# SCH_ELLIE_DISPLAY_PANEL_2023-12-06.net
KiCad netlist of a schematic drawn in EasyEDA
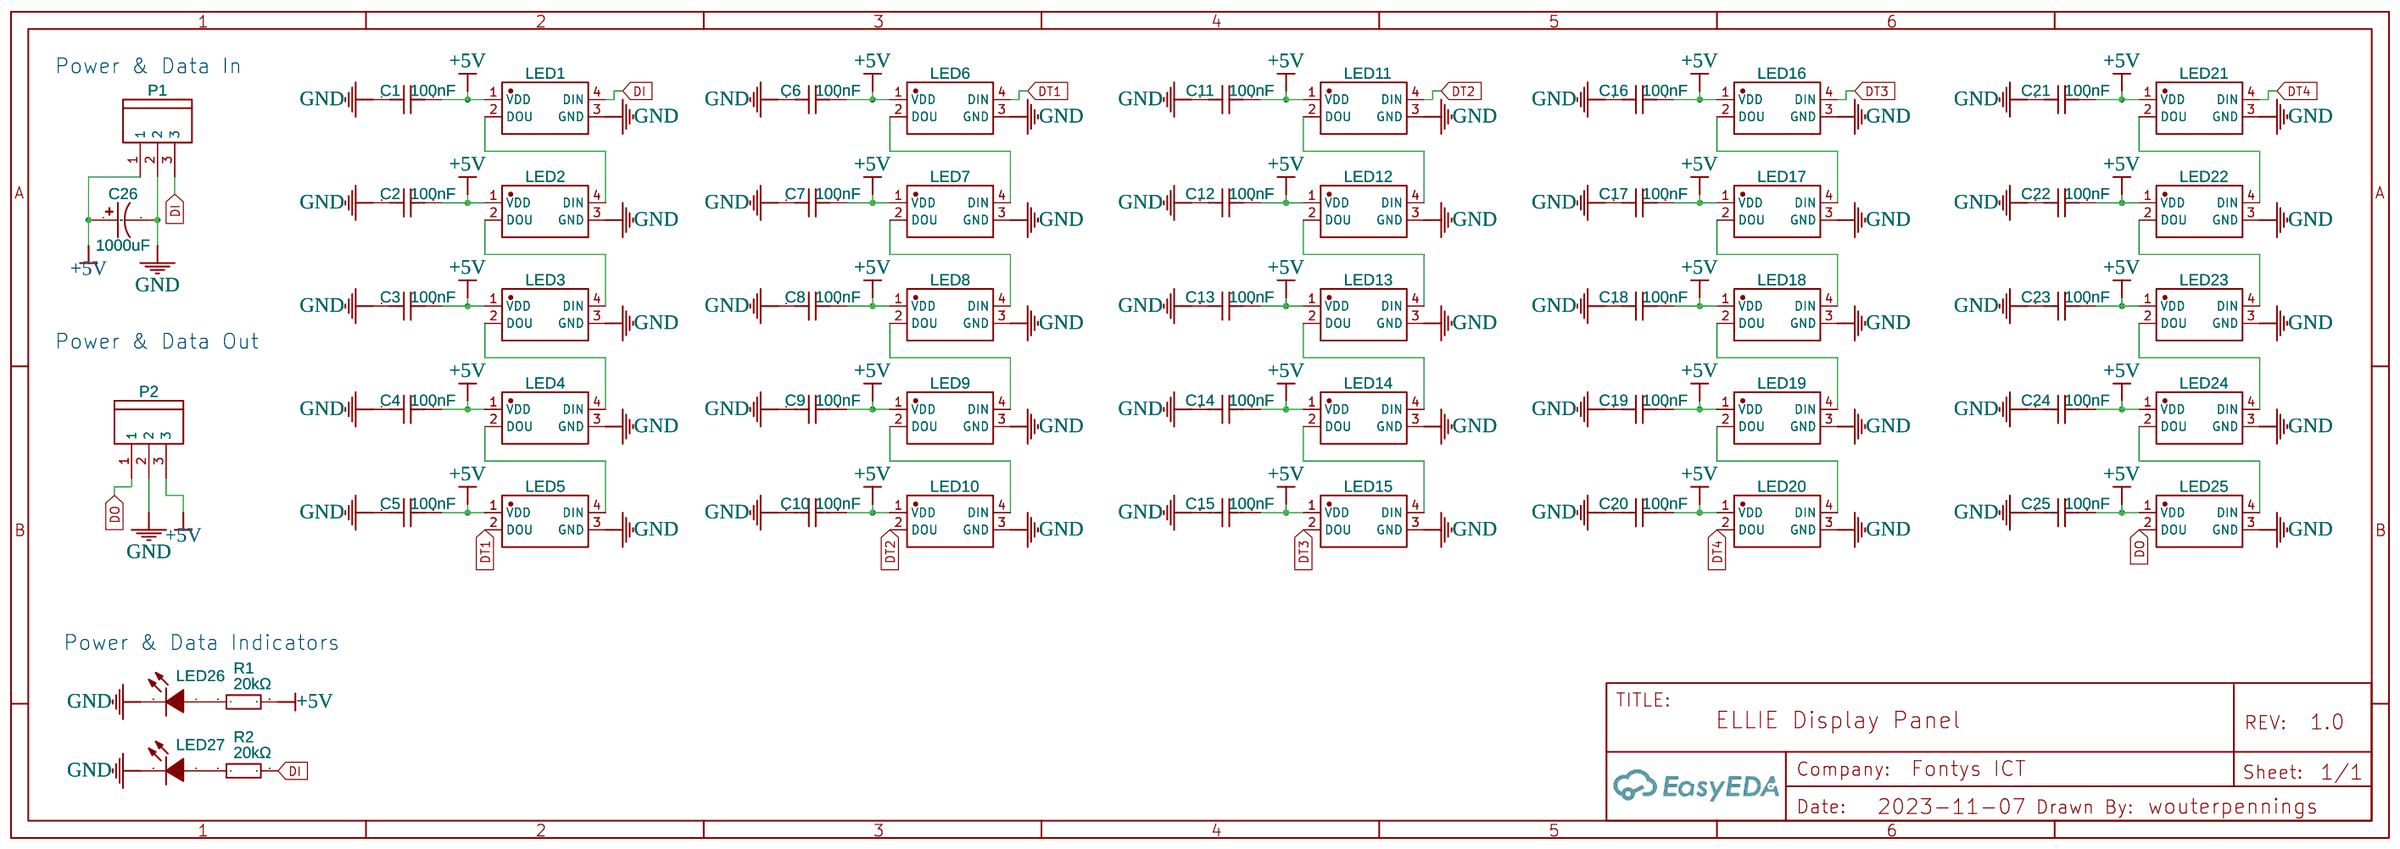
[diagram p0: schematic sheet]

(export (version "E")
  (design (tool "Eeschema 10.0.6"))
  (components
    (comp (ref "C1")
      (value "100nF")
      (fields
        (field (name "Manufacturer Part") "CC0402KRX7R7BB104")
        (field (name "Manufacturer") "YAGEO(国巨)")
      )
      (libsource (lib "") (part "CC0402KRX7R7BB104"))
    )
    (comp (ref "C2")
      (value "100nF")
      (fields
        (field (name "Manufacturer Part") "CC0402KRX7R7BB104")
        (field (name "Manufacturer") "YAGEO(国巨)")
      )
      (libsource (lib "") (part "CC0402KRX7R7BB104"))
    )
    (comp (ref "C3")
      (value "100nF")
      (fields
        (field (name "Manufacturer Part") "CC0402KRX7R7BB104")
        (field (name "Manufacturer") "YAGEO(国巨)")
      )
      (libsource (lib "") (part "CC0402KRX7R7BB104"))
    )
    (comp (ref "C4")
      (value "100nF")
      (fields
        (field (name "Manufacturer Part") "CC0402KRX7R7BB104")
        (field (name "Manufacturer") "YAGEO(国巨)")
      )
      (libsource (lib "") (part "CC0402KRX7R7BB104"))
    )
    (comp (ref "C5")
      (value "100nF")
      (fields
        (field (name "Manufacturer Part") "CC0402KRX7R7BB104")
        (field (name "Manufacturer") "YAGEO(国巨)")
      )
      (libsource (lib "") (part "CC0402KRX7R7BB104"))
    )
    (comp (ref "C6")
      (value "100nF")
      (fields
        (field (name "Manufacturer Part") "CC0402KRX7R7BB104")
        (field (name "Manufacturer") "YAGEO(国巨)")
      )
      (libsource (lib "") (part "CC0402KRX7R7BB104"))
    )
    (comp (ref "C7")
      (value "100nF")
      (fields
        (field (name "Manufacturer Part") "CC0402KRX7R7BB104")
        (field (name "Manufacturer") "YAGEO(国巨)")
      )
      (libsource (lib "") (part "CC0402KRX7R7BB104"))
    )
    (comp (ref "C8")
      (value "100nF")
      (fields
        (field (name "Manufacturer Part") "CC0402KRX7R7BB104")
        (field (name "Manufacturer") "YAGEO(国巨)")
      )
      (libsource (lib "") (part "CC0402KRX7R7BB104"))
    )
    (comp (ref "C9")
      (value "100nF")
      (fields
        (field (name "Manufacturer Part") "CC0402KRX7R7BB104")
        (field (name "Manufacturer") "YAGEO(国巨)")
      )
      (libsource (lib "") (part "CC0402KRX7R7BB104"))
    )
    (comp (ref "C10")
      (value "100nF")
      (fields
        (field (name "Manufacturer Part") "CC0402KRX7R7BB104")
        (field (name "Manufacturer") "YAGEO(国巨)")
      )
      (libsource (lib "") (part "CC0402KRX7R7BB104"))
    )
    (comp (ref "C11")
      (value "100nF")
      (fields
        (field (name "Manufacturer Part") "CC0402KRX7R7BB104")
        (field (name "Manufacturer") "YAGEO(国巨)")
      )
      (libsource (lib "") (part "CC0402KRX7R7BB104"))
    )
    (comp (ref "C12")
      (value "100nF")
      (fields
        (field (name "Manufacturer Part") "CC0402KRX7R7BB104")
        (field (name "Manufacturer") "YAGEO(国巨)")
      )
      (libsource (lib "") (part "CC0402KRX7R7BB104"))
    )
    (comp (ref "C13")
      (value "100nF")
      (fields
        (field (name "Manufacturer Part") "CC0402KRX7R7BB104")
        (field (name "Manufacturer") "YAGEO(国巨)")
      )
      (libsource (lib "") (part "CC0402KRX7R7BB104"))
    )
    (comp (ref "C14")
      (value "100nF")
      (fields
        (field (name "Manufacturer Part") "CC0402KRX7R7BB104")
        (field (name "Manufacturer") "YAGEO(国巨)")
      )
      (libsource (lib "") (part "CC0402KRX7R7BB104"))
    )
    (comp (ref "C15")
      (value "100nF")
      (fields
        (field (name "Manufacturer Part") "CC0402KRX7R7BB104")
        (field (name "Manufacturer") "YAGEO(国巨)")
      )
      (libsource (lib "") (part "CC0402KRX7R7BB104"))
    )
    (comp (ref "C16")
      (value "100nF")
      (fields
        (field (name "Manufacturer Part") "CC0402KRX7R7BB104")
        (field (name "Manufacturer") "YAGEO(国巨)")
      )
      (libsource (lib "") (part "CC0402KRX7R7BB104"))
    )
    (comp (ref "C17")
      (value "100nF")
      (fields
        (field (name "Manufacturer Part") "CC0402KRX7R7BB104")
        (field (name "Manufacturer") "YAGEO(国巨)")
      )
      (libsource (lib "") (part "CC0402KRX7R7BB104"))
    )
    (comp (ref "C18")
      (value "100nF")
      (fields
        (field (name "Manufacturer Part") "CC0402KRX7R7BB104")
        (field (name "Manufacturer") "YAGEO(国巨)")
      )
      (libsource (lib "") (part "CC0402KRX7R7BB104"))
    )
    (comp (ref "C19")
      (value "100nF")
      (fields
        (field (name "Manufacturer Part") "CC0402KRX7R7BB104")
        (field (name "Manufacturer") "YAGEO(国巨)")
      )
      (libsource (lib "") (part "CC0402KRX7R7BB104"))
    )
    (comp (ref "C20")
      (value "100nF")
      (fields
        (field (name "Manufacturer Part") "CC0402KRX7R7BB104")
        (field (name "Manufacturer") "YAGEO(国巨)")
      )
      (libsource (lib "") (part "CC0402KRX7R7BB104"))
    )
    (comp (ref "C21")
      (value "100nF")
      (fields
        (field (name "Manufacturer Part") "CC0402KRX7R7BB104")
        (field (name "Manufacturer") "YAGEO(国巨)")
      )
      (libsource (lib "") (part "CC0402KRX7R7BB104"))
    )
    (comp (ref "C22")
      (value "100nF")
      (fields
        (field (name "Manufacturer Part") "CC0402KRX7R7BB104")
        (field (name "Manufacturer") "YAGEO(国巨)")
      )
      (libsource (lib "") (part "CC0402KRX7R7BB104"))
    )
    (comp (ref "C23")
      (value "100nF")
      (fields
        (field (name "Manufacturer Part") "CC0402KRX7R7BB104")
        (field (name "Manufacturer") "YAGEO(国巨)")
      )
      (libsource (lib "") (part "CC0402KRX7R7BB104"))
    )
    (comp (ref "C24")
      (value "100nF")
      (fields
        (field (name "Manufacturer Part") "CC0402KRX7R7BB104")
        (field (name "Manufacturer") "YAGEO(国巨)")
      )
      (libsource (lib "") (part "CC0402KRX7R7BB104"))
    )
    (comp (ref "C25")
      (value "100nF")
      (fields
        (field (name "Manufacturer Part") "CC0402KRX7R7BB104")
        (field (name "Manufacturer") "YAGEO(国巨)")
      )
      (libsource (lib "") (part "CC0402KRX7R7BB104"))
    )
    (comp (ref "C26")
      (value "1000uF")
      (fields
        (field (name "Manufacturer Part") "01EC4294SHC1000UF25V")
        (field (name "Manufacturer") "KNSCHA(科尼盛)")
      )
      (libsource (lib "") (part "01EC4294SHC1000UF25V"))
    )
    (comp (ref "LED1")
      (value "XL-5050RGBC-WS2812B")
      (fields (field (name "Manufacturer") "XINGLIGHT(成兴光)"))
      (libsource (lib "") (part "XL-5050RGBC-WS2812B"))
    )
    (comp (ref "LED2")
      (value "XL-5050RGBC-WS2812B")
      (fields (field (name "Manufacturer") "XINGLIGHT(成兴光)"))
      (libsource (lib "") (part "XL-5050RGBC-WS2812B"))
    )
    (comp (ref "LED3")
      (value "XL-5050RGBC-WS2812B")
      (fields (field (name "Manufacturer") "XINGLIGHT(成兴光)"))
      (libsource (lib "") (part "XL-5050RGBC-WS2812B"))
    )
    (comp (ref "LED4")
      (value "XL-5050RGBC-WS2812B")
      (fields (field (name "Manufacturer") "XINGLIGHT(成兴光)"))
      (libsource (lib "") (part "XL-5050RGBC-WS2812B"))
    )
    (comp (ref "LED5")
      (value "XL-5050RGBC-WS2812B")
      (fields (field (name "Manufacturer") "XINGLIGHT(成兴光)"))
      (libsource (lib "") (part "XL-5050RGBC-WS2812B"))
    )
    (comp (ref "LED6")
      (value "XL-5050RGBC-WS2812B")
      (fields (field (name "Manufacturer") "XINGLIGHT(成兴光)"))
      (libsource (lib "") (part "XL-5050RGBC-WS2812B"))
    )
    (comp (ref "LED7")
      (value "XL-5050RGBC-WS2812B")
      (fields (field (name "Manufacturer") "XINGLIGHT(成兴光)"))
      (libsource (lib "") (part "XL-5050RGBC-WS2812B"))
    )
    (comp (ref "LED8")
      (value "XL-5050RGBC-WS2812B")
      (fields (field (name "Manufacturer") "XINGLIGHT(成兴光)"))
      (libsource (lib "") (part "XL-5050RGBC-WS2812B"))
    )
    (comp (ref "LED9")
      (value "XL-5050RGBC-WS2812B")
      (fields (field (name "Manufacturer") "XINGLIGHT(成兴光)"))
      (libsource (lib "") (part "XL-5050RGBC-WS2812B"))
    )
    (comp (ref "LED10")
      (value "XL-5050RGBC-WS2812B")
      (fields (field (name "Manufacturer") "XINGLIGHT(成兴光)"))
      (libsource (lib "") (part "XL-5050RGBC-WS2812B"))
    )
    (comp (ref "LED11")
      (value "XL-5050RGBC-WS2812B")
      (fields (field (name "Manufacturer") "XINGLIGHT(成兴光)"))
      (libsource (lib "") (part "XL-5050RGBC-WS2812B"))
    )
    (comp (ref "LED12")
      (value "XL-5050RGBC-WS2812B")
      (fields (field (name "Manufacturer") "XINGLIGHT(成兴光)"))
      (libsource (lib "") (part "XL-5050RGBC-WS2812B"))
    )
    (comp (ref "LED13")
      (value "XL-5050RGBC-WS2812B")
      (fields (field (name "Manufacturer") "XINGLIGHT(成兴光)"))
      (libsource (lib "") (part "XL-5050RGBC-WS2812B"))
    )
    (comp (ref "LED14")
      (value "XL-5050RGBC-WS2812B")
      (fields (field (name "Manufacturer") "XINGLIGHT(成兴光)"))
      (libsource (lib "") (part "XL-5050RGBC-WS2812B"))
    )
    (comp (ref "LED15")
      (value "XL-5050RGBC-WS2812B")
      (fields (field (name "Manufacturer") "XINGLIGHT(成兴光)"))
      (libsource (lib "") (part "XL-5050RGBC-WS2812B"))
    )
    (comp (ref "LED16")
      (value "XL-5050RGBC-WS2812B")
      (fields (field (name "Manufacturer") "XINGLIGHT(成兴光)"))
      (libsource (lib "") (part "XL-5050RGBC-WS2812B"))
    )
    (comp (ref "LED17")
      (value "XL-5050RGBC-WS2812B")
      (fields (field (name "Manufacturer") "XINGLIGHT(成兴光)"))
      (libsource (lib "") (part "XL-5050RGBC-WS2812B"))
    )
    (comp (ref "LED18")
      (value "XL-5050RGBC-WS2812B")
      (fields (field (name "Manufacturer") "XINGLIGHT(成兴光)"))
      (libsource (lib "") (part "XL-5050RGBC-WS2812B"))
    )
    (comp (ref "LED19")
      (value "XL-5050RGBC-WS2812B")
      (fields (field (name "Manufacturer") "XINGLIGHT(成兴光)"))
      (libsource (lib "") (part "XL-5050RGBC-WS2812B"))
    )
    (comp (ref "LED20")
      (value "XL-5050RGBC-WS2812B")
      (fields (field (name "Manufacturer") "XINGLIGHT(成兴光)"))
      (libsource (lib "") (part "XL-5050RGBC-WS2812B"))
    )
    (comp (ref "LED21")
      (value "XL-5050RGBC-WS2812B")
      (fields (field (name "Manufacturer") "XINGLIGHT(成兴光)"))
      (libsource (lib "") (part "XL-5050RGBC-WS2812B"))
    )
    (comp (ref "LED22")
      (value "XL-5050RGBC-WS2812B")
      (fields (field (name "Manufacturer") "XINGLIGHT(成兴光)"))
      (libsource (lib "") (part "XL-5050RGBC-WS2812B"))
    )
    (comp (ref "LED23")
      (value "XL-5050RGBC-WS2812B")
      (fields (field (name "Manufacturer") "XINGLIGHT(成兴光)"))
      (libsource (lib "") (part "XL-5050RGBC-WS2812B"))
    )
    (comp (ref "LED24")
      (value "XL-5050RGBC-WS2812B")
      (fields (field (name "Manufacturer") "XINGLIGHT(成兴光)"))
      (libsource (lib "") (part "XL-5050RGBC-WS2812B"))
    )
    (comp (ref "LED25")
      (value "XL-5050RGBC-WS2812B")
      (fields (field (name "Manufacturer") "XINGLIGHT(成兴光)"))
      (libsource (lib "") (part "XL-5050RGBC-WS2812B"))
    )
    (comp (ref "LED26")
      (value "SZYY0805R")
      (fields (field (name "Manufacturer") "yongyu(永裕光电)"))
      (libsource (lib "") (part "SZYY0805R"))
    )
    (comp (ref "LED27")
      (value "SZYY0805R")
      (fields (field (name "Manufacturer") "yongyu(永裕光电)"))
      (libsource (lib "") (part "SZYY0805R"))
    )
    (comp (ref "P1")
      (value "WJ500V-5.08-3P-14-00A")
      (fields
        (field (name "Manufacturer Part") "WJ500V-5.08-3P")
        (field (name "Manufacturer") "KANGNEX(康奈克斯电气)")
      )
      (libsource (lib "") (part "WJ500V-5.08-3P-14-00A"))
    )
    (comp (ref "P2")
      (value "WJ500V-5.08-3P-14-00A")
      (fields
        (field (name "Manufacturer Part") "WJ500V-5.08-3P")
        (field (name "Manufacturer") "KANGNEX(康奈克斯电气)")
      )
      (libsource (lib "") (part "WJ500V-5.08-3P-14-00A"))
    )
    (comp (ref "R1")
      (value "20kΩ")
      (fields
        (field (name "Manufacturer Part") "0603WAF2002T5E")
        (field (name "Manufacturer") "UNI-ROYAL(厚声)")
      )
      (libsource (lib "") (part "0603WAF2002T5E"))
    )
    (comp (ref "R2")
      (value "20kΩ")
      (fields
        (field (name "Manufacturer Part") "0603WAF2002T5E")
        (field (name "Manufacturer") "UNI-ROYAL(厚声)")
      )
      (libsource (lib "") (part "0603WAF2002T5E"))
    )
  )
  (nets
    (net (code "1") (name "+5V") (class "Default")
      (node (ref "C1") (pin "2") (pinfunction "2_2") (pintype "unspecified"))
      (node (ref "C10") (pin "2") (pinfunction "2_2") (pintype "unspecified"))
      (node (ref "C11") (pin "2") (pinfunction "2_2") (pintype "unspecified"))
      (node (ref "C12") (pin "2") (pinfunction "2_2") (pintype "unspecified"))
      (node (ref "C13") (pin "2") (pinfunction "2_2") (pintype "unspecified"))
      (node (ref "C14") (pin "2") (pinfunction "2_2") (pintype "unspecified"))
      (node (ref "C15") (pin "2") (pinfunction "2_2") (pintype "unspecified"))
      (node (ref "C16") (pin "2") (pinfunction "2_2") (pintype "unspecified"))
      (node (ref "C17") (pin "2") (pinfunction "2_2") (pintype "unspecified"))
      (node (ref "C18") (pin "2") (pinfunction "2_2") (pintype "unspecified"))
      (node (ref "C19") (pin "2") (pinfunction "2_2") (pintype "unspecified"))
      (node (ref "C2") (pin "2") (pinfunction "2_2") (pintype "unspecified"))
      (node (ref "C20") (pin "2") (pinfunction "2_2") (pintype "unspecified"))
      (node (ref "C21") (pin "2") (pinfunction "2_2") (pintype "unspecified"))
      (node (ref "C22") (pin "2") (pinfunction "2_2") (pintype "unspecified"))
      (node (ref "C23") (pin "2") (pinfunction "2_2") (pintype "unspecified"))
      (node (ref "C24") (pin "2") (pinfunction "2_2") (pintype "unspecified"))
      (node (ref "C25") (pin "2") (pinfunction "2_2") (pintype "unspecified"))
      (node (ref "C26") (pin "1") (pinfunction "1_1") (pintype "unspecified"))
      (node (ref "C3") (pin "2") (pinfunction "2_2") (pintype "unspecified"))
      (node (ref "C4") (pin "2") (pinfunction "2_2") (pintype "unspecified"))
      (node (ref "C5") (pin "2") (pinfunction "2_2") (pintype "unspecified"))
      (node (ref "C6") (pin "2") (pinfunction "2_2") (pintype "unspecified"))
      (node (ref "C7") (pin "2") (pinfunction "2_2") (pintype "unspecified"))
      (node (ref "C8") (pin "2") (pinfunction "2_2") (pintype "unspecified"))
      (node (ref "C9") (pin "2") (pinfunction "2_2") (pintype "unspecified"))
      (node (ref "LED1") (pin "1") (pinfunction "VDD_1") (pintype "unspecified"))
      (node (ref "LED10") (pin "1") (pinfunction "VDD_1") (pintype "unspecified"))
      (node (ref "LED11") (pin "1") (pinfunction "VDD_1") (pintype "unspecified"))
      (node (ref "LED12") (pin "1") (pinfunction "VDD_1") (pintype "unspecified"))
      (node (ref "LED13") (pin "1") (pinfunction "VDD_1") (pintype "unspecified"))
      (node (ref "LED14") (pin "1") (pinfunction "VDD_1") (pintype "unspecified"))
      (node (ref "LED15") (pin "1") (pinfunction "VDD_1") (pintype "unspecified"))
      (node (ref "LED16") (pin "1") (pinfunction "VDD_1") (pintype "unspecified"))
      (node (ref "LED17") (pin "1") (pinfunction "VDD_1") (pintype "unspecified"))
      (node (ref "LED18") (pin "1") (pinfunction "VDD_1") (pintype "unspecified"))
      (node (ref "LED19") (pin "1") (pinfunction "VDD_1") (pintype "unspecified"))
      (node (ref "LED2") (pin "1") (pinfunction "VDD_1") (pintype "unspecified"))
      (node (ref "LED20") (pin "1") (pinfunction "VDD_1") (pintype "unspecified"))
      (node (ref "LED21") (pin "1") (pinfunction "VDD_1") (pintype "unspecified"))
      (node (ref "LED22") (pin "1") (pinfunction "VDD_1") (pintype "unspecified"))
      (node (ref "LED23") (pin "1") (pinfunction "VDD_1") (pintype "unspecified"))
      (node (ref "LED24") (pin "1") (pinfunction "VDD_1") (pintype "unspecified"))
      (node (ref "LED25") (pin "1") (pinfunction "VDD_1") (pintype "unspecified"))
      (node (ref "LED3") (pin "1") (pinfunction "VDD_1") (pintype "unspecified"))
      (node (ref "LED4") (pin "1") (pinfunction "VDD_1") (pintype "unspecified"))
      (node (ref "LED5") (pin "1") (pinfunction "VDD_1") (pintype "unspecified"))
      (node (ref "LED6") (pin "1") (pinfunction "VDD_1") (pintype "unspecified"))
      (node (ref "LED7") (pin "1") (pinfunction "VDD_1") (pintype "unspecified"))
      (node (ref "LED8") (pin "1") (pinfunction "VDD_1") (pintype "unspecified"))
      (node (ref "LED9") (pin "1") (pinfunction "VDD_1") (pintype "unspecified"))
      (node (ref "P1") (pin "1") (pinfunction "1_1") (pintype "unspecified"))
      (node (ref "P2") (pin "3") (pinfunction "3_3") (pintype "unspecified"))
      (node (ref "R1") (pin "2") (pinfunction "2_2") (pintype "input"))
    )
    (net (code "2") (name "DI") (class "Default")
      (node (ref "LED1") (pin "4") (pinfunction "DIN_4") (pintype "unspecified"))
      (node (ref "P1") (pin "3") (pinfunction "3_3") (pintype "unspecified"))
      (node (ref "R2") (pin "2") (pinfunction "2_2") (pintype "input"))
    )
    (net (code "3") (name "DO") (class "Default")
      (node (ref "LED25") (pin "2") (pinfunction "DOU_2") (pintype "unspecified"))
      (node (ref "P2") (pin "1") (pinfunction "1_1") (pintype "unspecified"))
    )
    (net (code "4") (name "DT1") (class "Default")
      (node (ref "LED5") (pin "2") (pinfunction "DOU_2") (pintype "unspecified"))
      (node (ref "LED6") (pin "4") (pinfunction "DIN_4") (pintype "unspecified"))
    )
    (net (code "5") (name "DT2") (class "Default")
      (node (ref "LED10") (pin "2") (pinfunction "DOU_2") (pintype "unspecified"))
      (node (ref "LED11") (pin "4") (pinfunction "DIN_4") (pintype "unspecified"))
    )
    (net (code "6") (name "DT3") (class "Default")
      (node (ref "LED15") (pin "2") (pinfunction "DOU_2") (pintype "unspecified"))
      (node (ref "LED16") (pin "4") (pinfunction "DIN_4") (pintype "unspecified"))
    )
    (net (code "7") (name "DT4") (class "Default")
      (node (ref "LED20") (pin "2") (pinfunction "DOU_2") (pintype "unspecified"))
      (node (ref "LED21") (pin "4") (pinfunction "DIN_4") (pintype "unspecified"))
    )
    (net (code "8") (name "GND") (class "Default")
      (node (ref "C1") (pin "1") (pinfunction "1_1") (pintype "unspecified"))
      (node (ref "C10") (pin "1") (pinfunction "1_1") (pintype "unspecified"))
      (node (ref "C11") (pin "1") (pinfunction "1_1") (pintype "unspecified"))
      (node (ref "C12") (pin "1") (pinfunction "1_1") (pintype "unspecified"))
      (node (ref "C13") (pin "1") (pinfunction "1_1") (pintype "unspecified"))
      (node (ref "C14") (pin "1") (pinfunction "1_1") (pintype "unspecified"))
      (node (ref "C15") (pin "1") (pinfunction "1_1") (pintype "unspecified"))
      (node (ref "C16") (pin "1") (pinfunction "1_1") (pintype "unspecified"))
      (node (ref "C17") (pin "1") (pinfunction "1_1") (pintype "unspecified"))
      (node (ref "C18") (pin "1") (pinfunction "1_1") (pintype "unspecified"))
      (node (ref "C19") (pin "1") (pinfunction "1_1") (pintype "unspecified"))
      (node (ref "C2") (pin "1") (pinfunction "1_1") (pintype "unspecified"))
      (node (ref "C20") (pin "1") (pinfunction "1_1") (pintype "unspecified"))
      (node (ref "C21") (pin "1") (pinfunction "1_1") (pintype "unspecified"))
      (node (ref "C22") (pin "1") (pinfunction "1_1") (pintype "unspecified"))
      (node (ref "C23") (pin "1") (pinfunction "1_1") (pintype "unspecified"))
      (node (ref "C24") (pin "1") (pinfunction "1_1") (pintype "unspecified"))
      (node (ref "C25") (pin "1") (pinfunction "1_1") (pintype "unspecified"))
      (node (ref "C26") (pin "2") (pinfunction "2_2") (pintype "unspecified"))
      (node (ref "C3") (pin "1") (pinfunction "1_1") (pintype "unspecified"))
      (node (ref "C4") (pin "1") (pinfunction "1_1") (pintype "unspecified"))
      (node (ref "C5") (pin "1") (pinfunction "1_1") (pintype "unspecified"))
      (node (ref "C6") (pin "1") (pinfunction "1_1") (pintype "unspecified"))
      (node (ref "C7") (pin "1") (pinfunction "1_1") (pintype "unspecified"))
      (node (ref "C8") (pin "1") (pinfunction "1_1") (pintype "unspecified"))
      (node (ref "C9") (pin "1") (pinfunction "1_1") (pintype "unspecified"))
      (node (ref "LED1") (pin "3") (pinfunction "GND_3") (pintype "unspecified"))
      (node (ref "LED10") (pin "3") (pinfunction "GND_3") (pintype "unspecified"))
      (node (ref "LED11") (pin "3") (pinfunction "GND_3") (pintype "unspecified"))
      (node (ref "LED12") (pin "3") (pinfunction "GND_3") (pintype "unspecified"))
      (node (ref "LED13") (pin "3") (pinfunction "GND_3") (pintype "unspecified"))
      (node (ref "LED14") (pin "3") (pinfunction "GND_3") (pintype "unspecified"))
      (node (ref "LED15") (pin "3") (pinfunction "GND_3") (pintype "unspecified"))
      (node (ref "LED16") (pin "3") (pinfunction "GND_3") (pintype "unspecified"))
      (node (ref "LED17") (pin "3") (pinfunction "GND_3") (pintype "unspecified"))
      (node (ref "LED18") (pin "3") (pinfunction "GND_3") (pintype "unspecified"))
      (node (ref "LED19") (pin "3") (pinfunction "GND_3") (pintype "unspecified"))
      (node (ref "LED2") (pin "3") (pinfunction "GND_3") (pintype "unspecified"))
      (node (ref "LED20") (pin "3") (pinfunction "GND_3") (pintype "unspecified"))
      (node (ref "LED21") (pin "3") (pinfunction "GND_3") (pintype "unspecified"))
      (node (ref "LED22") (pin "3") (pinfunction "GND_3") (pintype "unspecified"))
      (node (ref "LED23") (pin "3") (pinfunction "GND_3") (pintype "unspecified"))
      (node (ref "LED24") (pin "3") (pinfunction "GND_3") (pintype "unspecified"))
      (node (ref "LED25") (pin "3") (pinfunction "GND_3") (pintype "unspecified"))
      (node (ref "LED26") (pin "2") (pinfunction "-_2") (pintype "unspecified"))
      (node (ref "LED27") (pin "2") (pinfunction "-_2") (pintype "unspecified"))
      (node (ref "LED3") (pin "3") (pinfunction "GND_3") (pintype "unspecified"))
      (node (ref "LED4") (pin "3") (pinfunction "GND_3") (pintype "unspecified"))
      (node (ref "LED5") (pin "3") (pinfunction "GND_3") (pintype "unspecified"))
      (node (ref "LED6") (pin "3") (pinfunction "GND_3") (pintype "unspecified"))
      (node (ref "LED7") (pin "3") (pinfunction "GND_3") (pintype "unspecified"))
      (node (ref "LED8") (pin "3") (pinfunction "GND_3") (pintype "unspecified"))
      (node (ref "LED9") (pin "3") (pinfunction "GND_3") (pintype "unspecified"))
      (node (ref "P1") (pin "2") (pinfunction "2_2") (pintype "unspecified"))
      (node (ref "P2") (pin "2") (pinfunction "2_2") (pintype "unspecified"))
    )
    (net (code "9") (name "Net-(LED1-DOU)") (class "Default")
      (node (ref "LED1") (pin "2") (pinfunction "DOU_2") (pintype "unspecified"))
      (node (ref "LED2") (pin "4") (pinfunction "DIN_4") (pintype "unspecified"))
    )
    (net (code "10") (name "Net-(LED2-DOU)") (class "Default")
      (node (ref "LED2") (pin "2") (pinfunction "DOU_2") (pintype "unspecified"))
      (node (ref "LED3") (pin "4") (pinfunction "DIN_4") (pintype "unspecified"))
    )
    (net (code "11") (name "Net-(LED3-DOU)") (class "Default")
      (node (ref "LED3") (pin "2") (pinfunction "DOU_2") (pintype "unspecified"))
      (node (ref "LED4") (pin "4") (pinfunction "DIN_4") (pintype "unspecified"))
    )
    (net (code "12") (name "Net-(LED4-DOU)") (class "Default")
      (node (ref "LED4") (pin "2") (pinfunction "DOU_2") (pintype "unspecified"))
      (node (ref "LED5") (pin "4") (pinfunction "DIN_4") (pintype "unspecified"))
    )
    (net (code "13") (name "Net-(LED6-DOU)") (class "Default")
      (node (ref "LED6") (pin "2") (pinfunction "DOU_2") (pintype "unspecified"))
      (node (ref "LED7") (pin "4") (pinfunction "DIN_4") (pintype "unspecified"))
    )
    (net (code "14") (name "Net-(LED7-DOU)") (class "Default")
      (node (ref "LED7") (pin "2") (pinfunction "DOU_2") (pintype "unspecified"))
      (node (ref "LED8") (pin "4") (pinfunction "DIN_4") (pintype "unspecified"))
    )
    (net (code "15") (name "Net-(LED8-DOU)") (class "Default")
      (node (ref "LED8") (pin "2") (pinfunction "DOU_2") (pintype "unspecified"))
      (node (ref "LED9") (pin "4") (pinfunction "DIN_4") (pintype "unspecified"))
    )
    (net (code "16") (name "Net-(LED10-DIN)") (class "Default")
      (node (ref "LED10") (pin "4") (pinfunction "DIN_4") (pintype "unspecified"))
      (node (ref "LED9") (pin "2") (pinfunction "DOU_2") (pintype "unspecified"))
    )
    (net (code "17") (name "Net-(LED11-DOU)") (class "Default")
      (node (ref "LED11") (pin "2") (pinfunction "DOU_2") (pintype "unspecified"))
      (node (ref "LED12") (pin "4") (pinfunction "DIN_4") (pintype "unspecified"))
    )
    (net (code "18") (name "Net-(LED12-DOU)") (class "Default")
      (node (ref "LED12") (pin "2") (pinfunction "DOU_2") (pintype "unspecified"))
      (node (ref "LED13") (pin "4") (pinfunction "DIN_4") (pintype "unspecified"))
    )
    (net (code "19") (name "Net-(LED13-DOU)") (class "Default")
      (node (ref "LED13") (pin "2") (pinfunction "DOU_2") (pintype "unspecified"))
      (node (ref "LED14") (pin "4") (pinfunction "DIN_4") (pintype "unspecified"))
    )
    (net (code "20") (name "Net-(LED14-DOU)") (class "Default")
      (node (ref "LED14") (pin "2") (pinfunction "DOU_2") (pintype "unspecified"))
      (node (ref "LED15") (pin "4") (pinfunction "DIN_4") (pintype "unspecified"))
    )
    (net (code "21") (name "Net-(LED16-DOU)") (class "Default")
      (node (ref "LED16") (pin "2") (pinfunction "DOU_2") (pintype "unspecified"))
      (node (ref "LED17") (pin "4") (pinfunction "DIN_4") (pintype "unspecified"))
    )
    (net (code "22") (name "Net-(LED17-DOU)") (class "Default")
      (node (ref "LED17") (pin "2") (pinfunction "DOU_2") (pintype "unspecified"))
      (node (ref "LED18") (pin "4") (pinfunction "DIN_4") (pintype "unspecified"))
    )
    (net (code "23") (name "Net-(LED18-DOU)") (class "Default")
      (node (ref "LED18") (pin "2") (pinfunction "DOU_2") (pintype "unspecified"))
      (node (ref "LED19") (pin "4") (pinfunction "DIN_4") (pintype "unspecified"))
    )
    (net (code "24") (name "Net-(LED19-DOU)") (class "Default")
      (node (ref "LED19") (pin "2") (pinfunction "DOU_2") (pintype "unspecified"))
      (node (ref "LED20") (pin "4") (pinfunction "DIN_4") (pintype "unspecified"))
    )
    (net (code "25") (name "Net-(LED21-DOU)") (class "Default")
      (node (ref "LED21") (pin "2") (pinfunction "DOU_2") (pintype "unspecified"))
      (node (ref "LED22") (pin "4") (pinfunction "DIN_4") (pintype "unspecified"))
    )
    (net (code "26") (name "Net-(LED22-DOU)") (class "Default")
      (node (ref "LED22") (pin "2") (pinfunction "DOU_2") (pintype "unspecified"))
      (node (ref "LED23") (pin "4") (pinfunction "DIN_4") (pintype "unspecified"))
    )
    (net (code "27") (name "Net-(LED23-DOU)") (class "Default")
      (node (ref "LED23") (pin "2") (pinfunction "DOU_2") (pintype "unspecified"))
      (node (ref "LED24") (pin "4") (pinfunction "DIN_4") (pintype "unspecified"))
    )
    (net (code "28") (name "Net-(LED24-DOU)") (class "Default")
      (node (ref "LED24") (pin "2") (pinfunction "DOU_2") (pintype "unspecified"))
      (node (ref "LED25") (pin "4") (pinfunction "DIN_4") (pintype "unspecified"))
    )
    (net (code "29") (name "Net-(LED26-+)") (class "Default")
      (node (ref "LED26") (pin "1") (pinfunction "+_1") (pintype "unspecified"))
      (node (ref "R1") (pin "1") (pinfunction "1_1") (pintype "input"))
    )
    (net (code "30") (name "Net-(LED27-+)") (class "Default")
      (node (ref "LED27") (pin "1") (pinfunction "+_1") (pintype "unspecified"))
      (node (ref "R2") (pin "1") (pinfunction "1_1") (pintype "input"))
    )
  )
)
